# AudioPreAmp-LM741-TO99.net
KiCad netlist of a schematic drawn in EAGLE
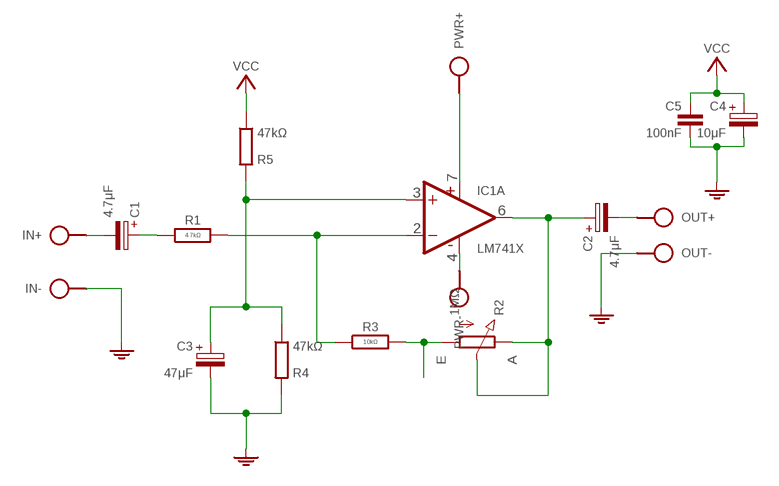
[diagram p0: schematic, sheet 1]

(export (version "E")
  (design (tool "Eeschema 10.0.6"))
  (components
    (comp (ref "C1")
      (value "4.7μF")
      (footprint "eagle-import:E2.5-4_V")
      (libsource (lib "eagle-import") (part "CPOLE2,5-4/V"))
    )
    (comp (ref "C2")
      (value "4.7μF")
      (footprint "eagle-import:E5-4")
      (libsource (lib "eagle-import") (part "CPOLE5-4"))
    )
    (comp (ref "C3")
      (value "47μF")
      (footprint "eagle-import:E2,5-4")
      (libsource (lib "eagle-import") (part "CPOLE2,5-4"))
    )
    (comp (ref "C4")
      (value "10μF")
      (footprint "eagle-import:E2,5-3")
      (libsource (lib "eagle-import") (part "CPOLE2,5-3"))
    )
    (comp (ref "C5")
      (value "100nF")
      (footprint "eagle-import:C050-020X044_V")
      (libsource (lib "eagle-import") (part "C050-020X044/V"))
    )
    (comp (ref "IC1")
      (value "LM741X")
      (footprint "eagle-import:TO99-X")
      (libsource (lib "eagle-import") (part "LM741X"))
    )
    (comp (ref "IN")
      (value "SPAD+--+")
      (footprint "eagle-import:SPAD-+")
      (libsource (lib "eagle-import") (part "SPAD+--+"))
    )
    (comp (ref "OUT")
      (value "SPAD+-+-")
      (footprint "eagle-import:SPAD+-")
      (libsource (lib "eagle-import") (part "SPAD+-+-"))
    )
    (comp (ref "PWR+")
      (value "HPORT")
      (footprint "eagle-import:SPAD")
      (libsource (lib "eagle-import") (part "HPORT"))
    )
    (comp (ref "PWR-")
      (value "HPORT")
      (footprint "eagle-import:SPAD")
      (libsource (lib "eagle-import") (part "HPORT"))
    )
    (comp (ref "R1")
      (value "4.7kΩ")
      (footprint "eagle-import:0204_10")
      (libsource (lib "eagle-import") (part "R-H0204/10"))
    )
    (comp (ref "R2")
      (value "1MΩ")
      (footprint "eagle-import:CONN-3P")
      (libsource (lib "eagle-import") (part "POT-3P"))
    )
    (comp (ref "R3")
      (value "10kΩ")
      (footprint "eagle-import:0204_10-V")
      (libsource (lib "eagle-import") (part "R-H0204/10-V"))
    )
    (comp (ref "R4")
      (value "47kΩ")
      (footprint "eagle-import:0204_10-V")
      (libsource (lib "eagle-import") (part "R0204/10-V"))
    )
    (comp (ref "R5")
      (value "47kΩ")
      (footprint "eagle-import:0204_10")
      (libsource (lib "eagle-import") (part "R0204/10"))
    )
  )
  (nets
    (net (code "1") (name "GND") (class "Default")
      (node (ref "C3") (pin "-") (pinfunction "-_-") (pintype "passive"))
      (node (ref "C4") (pin "-") (pinfunction "-_-") (pintype "passive"))
      (node (ref "C5") (pin "2") (pinfunction "2_2") (pintype "passive"))
      (node (ref "IN") (pin "1") (pinfunction "P$1_1") (pintype "passive"))
      (node (ref "OUT") (pin "1") (pinfunction "P$1_1") (pintype "passive"))
      (node (ref "R4") (pin "1") (pinfunction "2_1") (pintype "passive"))
    )
    (net (code "2") (name "Net-(C1-Pad+)") (class "Default")
      (node (ref "C1") (pin "+") (pinfunction "+_+") (pintype "passive"))
      (node (ref "R1") (pin "1") (pinfunction "1_1") (pintype "passive"))
    )
    (net (code "3") (name "Net-(IC1A-V+)") (class "Default")
      (node (ref "IC1") (pin "7") (pinfunction "V+_7") (pintype "power_in"))
      (node (ref "PWR+") (pin "1") (pinfunction "P$1_1") (pintype "passive"))
    )
    (net (code "4") (name "Net-(IC1A-V-)") (class "Default")
      (node (ref "IC1") (pin "4") (pinfunction "V-_4") (pintype "power_in"))
      (node (ref "PWR-") (pin "1") (pinfunction "P$1_1") (pintype "passive"))
    )
    (net (code "5") (name "Net-(IC1B-+IN)") (class "Default")
      (node (ref "C3") (pin "+") (pinfunction "+_+") (pintype "passive"))
      (node (ref "IC1") (pin "3") (pinfunction "+IN_3") (pintype "input"))
      (node (ref "R4") (pin "2") (pinfunction "1_2") (pintype "passive"))
      (node (ref "R5") (pin "1") (pinfunction "2_1") (pintype "passive"))
    )
    (net (code "6") (name "Net-(IC1B--IN)") (class "Default")
      (node (ref "IC1") (pin "2") (pinfunction "-IN_2") (pintype "input"))
      (node (ref "R1") (pin "2") (pinfunction "2_2") (pintype "passive"))
      (node (ref "R3") (pin "1") (pinfunction "1_1") (pintype "passive"))
    )
    (net (code "7") (name "Net-(IC1B-OUT)") (class "Default")
      (node (ref "C2") (pin "+") (pinfunction "+_+") (pintype "passive"))
      (node (ref "IC1") (pin "6") (pinfunction "OUT_6") (pintype "output"))
      (node (ref "R2") (pin "2") (pinfunction "S_2") (pintype "passive"))
      (node (ref "R2") (pin "3") (pinfunction "E_3") (pintype "passive"))
    )
    (net (code "8") (name "Net-(INA-P$1)") (class "Default")
      (node (ref "C1") (pin "-") (pinfunction "-_-") (pintype "passive"))
      (node (ref "IN") (pin "2") (pinfunction "P$1_2") (pintype "passive"))
    )
    (net (code "9") (name "Net-(OUTA-P$1)") (class "Default")
      (node (ref "C2") (pin "-") (pinfunction "-_-") (pintype "passive"))
      (node (ref "OUT") (pin "2") (pinfunction "P$1_2") (pintype "passive"))
    )
    (net (code "10") (name "Net-(R2-A)") (class "Default")
      (node (ref "R2") (pin "1") (pinfunction "A_1") (pintype "passive"))
      (node (ref "R3") (pin "2") (pinfunction "2_2") (pintype "passive"))
    )
    (net (code "11") (name "VCC") (class "Default")
      (node (ref "C4") (pin "+") (pinfunction "+_+") (pintype "passive"))
      (node (ref "C5") (pin "1") (pinfunction "1_1") (pintype "passive"))
      (node (ref "R5") (pin "2") (pinfunction "1_2") (pintype "passive"))
    )
  )
)
